# Mechanical.net
KiCad netlist of a schematic drawn in Altium Designer
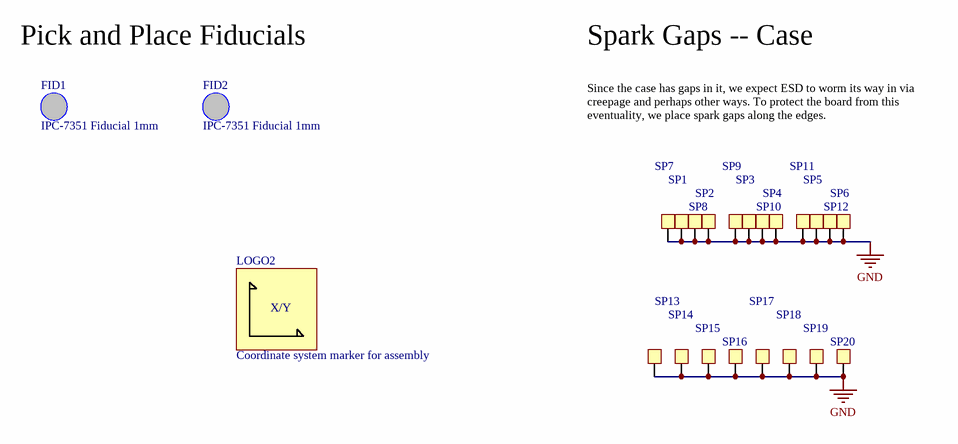
[diagram p0: Mechanical.SchDoc]

(export (version "E")
  (design (tool "Eeschema 10.0.6"))
  (components
    (comp (ref "FID1")
      (value "IPC-7351 Fiducial 1mm")
      (footprint "FIDUCIAL_1.5")
      (libsource (lib "Mechanical") (part "FIDUCIAL_1.5"))
    )
    (comp (ref "FID2")
      (value "IPC-7351 Fiducial 1mm")
      (footprint "FIDUCIAL_1.5")
      (libsource (lib "Mechanical") (part "FIDUCIAL_1.5"))
    )
    (comp (ref "LOGO2")
      (value "Coordinate system marker for assembly")
      (footprint "Coordinate System")
      (libsource (lib "Graphics") (part "CoordinateSystem"))
    )
    (comp (ref "SP1")
      (value "Spark Gap")
      (footprint "SparkGap")
      (description "Open square pad for spark gapping")
      (libsource (lib "PCBFeatures") (part "Spark Gap"))
    )
    (comp (ref "SP2")
      (value "Spark Gap")
      (footprint "SparkGap")
      (description "Open square pad for spark gapping")
      (libsource (lib "PCBFeatures") (part "Spark Gap"))
    )
    (comp (ref "SP3")
      (value "Spark Gap")
      (footprint "SparkGap")
      (description "Open square pad for spark gapping")
      (libsource (lib "PCBFeatures") (part "Spark Gap"))
    )
    (comp (ref "SP4")
      (value "Spark Gap")
      (footprint "SparkGap")
      (description "Open square pad for spark gapping")
      (libsource (lib "PCBFeatures") (part "Spark Gap"))
    )
    (comp (ref "SP5")
      (value "Spark Gap")
      (footprint "SparkGap")
      (description "Open square pad for spark gapping")
      (libsource (lib "PCBFeatures") (part "Spark Gap"))
    )
    (comp (ref "SP6")
      (value "Spark Gap")
      (footprint "SparkGap")
      (description "Open square pad for spark gapping")
      (libsource (lib "PCBFeatures") (part "Spark Gap"))
    )
    (comp (ref "SP7")
      (value "Spark Gap")
      (footprint "SparkGap")
      (description "Open square pad for spark gapping")
      (libsource (lib "PCBFeatures") (part "Spark Gap"))
    )
    (comp (ref "SP8")
      (value "Spark Gap")
      (footprint "SparkGap")
      (description "Open square pad for spark gapping")
      (libsource (lib "PCBFeatures") (part "Spark Gap"))
    )
    (comp (ref "SP9")
      (value "Spark Gap")
      (footprint "SparkGap")
      (description "Open square pad for spark gapping")
      (libsource (lib "PCBFeatures") (part "Spark Gap"))
    )
    (comp (ref "SP10")
      (value "Spark Gap")
      (footprint "SparkGap")
      (description "Open square pad for spark gapping")
      (libsource (lib "PCBFeatures") (part "Spark Gap"))
    )
    (comp (ref "SP11")
      (value "Spark Gap")
      (footprint "SparkGap")
      (description "Open square pad for spark gapping")
      (libsource (lib "PCBFeatures") (part "Spark Gap"))
    )
    (comp (ref "SP12")
      (value "Spark Gap")
      (footprint "SparkGap")
      (description "Open square pad for spark gapping")
      (libsource (lib "PCBFeatures") (part "Spark Gap"))
    )
    (comp (ref "SP13")
      (value "Spark Gap")
      (footprint "SparkGap")
      (description "Open square pad for spark gapping")
      (libsource (lib "PCBFeatures") (part "Spark Gap"))
    )
    (comp (ref "SP14")
      (value "Spark Gap")
      (footprint "SparkGap")
      (description "Open square pad for spark gapping")
      (libsource (lib "PCBFeatures") (part "Spark Gap"))
    )
    (comp (ref "SP15")
      (value "Spark Gap")
      (footprint "SparkGap")
      (description "Open square pad for spark gapping")
      (libsource (lib "PCBFeatures") (part "Spark Gap"))
    )
    (comp (ref "SP16")
      (value "Spark Gap")
      (footprint "SparkGap")
      (description "Open square pad for spark gapping")
      (libsource (lib "PCBFeatures") (part "Spark Gap"))
    )
    (comp (ref "SP17")
      (value "Spark Gap")
      (footprint "SparkGap")
      (description "Open square pad for spark gapping")
      (libsource (lib "PCBFeatures") (part "Spark Gap"))
    )
    (comp (ref "SP18")
      (value "Spark Gap")
      (footprint "SparkGap")
      (description "Open square pad for spark gapping")
      (libsource (lib "PCBFeatures") (part "Spark Gap"))
    )
    (comp (ref "SP19")
      (value "Spark Gap")
      (footprint "SparkGap")
      (description "Open square pad for spark gapping")
      (libsource (lib "PCBFeatures") (part "Spark Gap"))
    )
    (comp (ref "SP20")
      (value "Spark Gap")
      (footprint "SparkGap")
      (description "Open square pad for spark gapping")
      (libsource (lib "PCBFeatures") (part "Spark Gap"))
    )
  )
  (nets
    (net (code "1") (name "GND") (class "Default")
      (node (ref "SP1") (pin "1") (pinfunction "1_1") (pintype "passive"))
      (node (ref "SP10") (pin "1") (pinfunction "1_1") (pintype "passive"))
      (node (ref "SP11") (pin "1") (pinfunction "1_1") (pintype "passive"))
      (node (ref "SP12") (pin "1") (pinfunction "1_1") (pintype "passive"))
      (node (ref "SP13") (pin "1") (pinfunction "1_1") (pintype "passive"))
      (node (ref "SP14") (pin "1") (pinfunction "1_1") (pintype "passive"))
      (node (ref "SP15") (pin "1") (pinfunction "1_1") (pintype "passive"))
      (node (ref "SP16") (pin "1") (pinfunction "1_1") (pintype "passive"))
      (node (ref "SP17") (pin "1") (pinfunction "1_1") (pintype "passive"))
      (node (ref "SP18") (pin "1") (pinfunction "1_1") (pintype "passive"))
      (node (ref "SP19") (pin "1") (pinfunction "1_1") (pintype "passive"))
      (node (ref "SP2") (pin "1") (pinfunction "1_1") (pintype "passive"))
      (node (ref "SP20") (pin "1") (pinfunction "1_1") (pintype "passive"))
      (node (ref "SP3") (pin "1") (pinfunction "1_1") (pintype "passive"))
      (node (ref "SP4") (pin "1") (pinfunction "1_1") (pintype "passive"))
      (node (ref "SP5") (pin "1") (pinfunction "1_1") (pintype "passive"))
      (node (ref "SP6") (pin "1") (pinfunction "1_1") (pintype "passive"))
      (node (ref "SP7") (pin "1") (pinfunction "1_1") (pintype "passive"))
      (node (ref "SP8") (pin "1") (pinfunction "1_1") (pintype "passive"))
      (node (ref "SP9") (pin "1") (pinfunction "1_1") (pintype "passive"))
    )
    (net (code "2") (name "unconnected-(FID1-Pad1)") (class "Default")
      (node (ref "FID1") (pin "1") (pinfunction "1_1") (pintype "passive"))
    )
    (net (code "3") (name "unconnected-(FID2-Pad1)") (class "Default")
      (node (ref "FID2") (pin "1") (pinfunction "1_1") (pintype "passive"))
    )
  )
)
